# dc_dc.net
KiCad netlist of a schematic drawn in Altium Designer
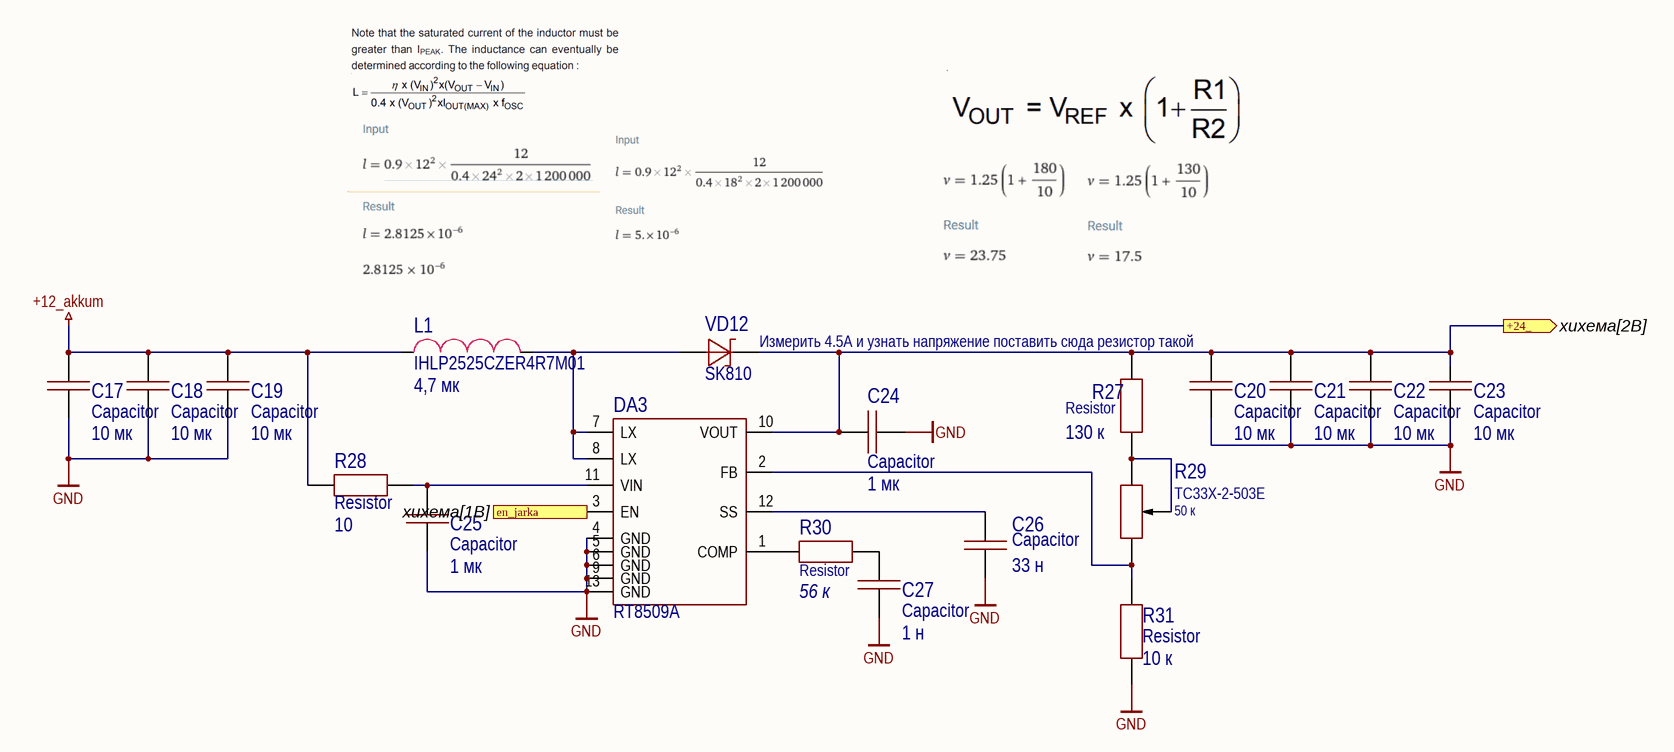
[diagram p0: dc dc жарить панели.SchDoc]

(export (version "E")
  (design (tool "Eeschema 10.0.6"))
  (components
    (comp (ref "C17")
      (value "Capacitor")
      (footprint "1210C")
      (description "Конденсатор")
      (fields
        (field (name "ALTIUM_VALUE") "10 мк")
        (field (name "PART NUMBER") "Capacitor_10u_10_35V_X7R_1210C")
        (field (name "TOLERANCE") "0,1")
      )
      (libsource (lib "Hydrolib") (part "Capacitor"))
    )
    (comp (ref "C18")
      (value "Capacitor")
      (footprint "1210C")
      (description "Конденсатор")
      (fields
        (field (name "ALTIUM_VALUE") "10 мк")
        (field (name "PART NUMBER") "Capacitor_10u_10_35V_X7R_1210C")
        (field (name "TOLERANCE") "0,1")
      )
      (libsource (lib "Hydrolib") (part "Capacitor"))
    )
    (comp (ref "C19")
      (value "Capacitor")
      (footprint "1210C")
      (description "Конденсатор")
      (fields
        (field (name "ALTIUM_VALUE") "10 мк")
        (field (name "PART NUMBER") "Capacitor_10u_10_35V_X7R_1210C")
        (field (name "TOLERANCE") "0,1")
      )
      (libsource (lib "Hydrolib") (part "Capacitor"))
    )
    (comp (ref "C20")
      (value "Capacitor")
      (footprint "1210C")
      (description "Конденсатор")
      (fields
        (field (name "ALTIUM_VALUE") "10 мк")
        (field (name "PART NUMBER") "Capacitor_10u_10_35V_X7R_1210C")
        (field (name "TOLERANCE") "0,1")
      )
      (libsource (lib "Hydrolib") (part "Capacitor"))
    )
    (comp (ref "C21")
      (value "Capacitor")
      (footprint "1210C")
      (description "Конденсатор")
      (fields
        (field (name "ALTIUM_VALUE") "10 мк")
        (field (name "PART NUMBER") "Capacitor_10u_10_35V_X7R_1210C")
        (field (name "TOLERANCE") "0,1")
      )
      (libsource (lib "Hydrolib") (part "Capacitor"))
    )
    (comp (ref "C22")
      (value "Capacitor")
      (footprint "1210C")
      (description "Конденсатор")
      (fields
        (field (name "ALTIUM_VALUE") "10 мк")
        (field (name "PART NUMBER") "Capacitor_10u_10_35V_X7R_1210C")
        (field (name "TOLERANCE") "0,1")
      )
      (libsource (lib "Hydrolib") (part "Capacitor"))
    )
    (comp (ref "C23")
      (value "Capacitor")
      (footprint "1210C")
      (description "Конденсатор")
      (fields
        (field (name "ALTIUM_VALUE") "10 мк")
        (field (name "PART NUMBER") "Capacitor_10u_10_35V_X7R_1210C")
        (field (name "TOLERANCE") "0,1")
      )
      (libsource (lib "Hydrolib") (part "Capacitor"))
    )
    (comp (ref "C24")
      (value "Capacitor")
      (footprint "0603C")
      (description "Конденсатор")
      (fields
        (field (name "ALTIUM_VALUE") "1 мк")
        (field (name "PART NUMBER") "Capacitor_1u_10_50V_X7R_0603C")
        (field (name "TOLERANCE") "0,1")
      )
      (libsource (lib "Hydrolib") (part "Capacitor"))
    )
    (comp (ref "C25")
      (value "Capacitor")
      (footprint "0603C")
      (description "Конденсатор")
      (fields
        (field (name "ALTIUM_VALUE") "1 мк")
        (field (name "PART NUMBER") "Capacitor_1u_10_50V_X7R_0603C")
        (field (name "TOLERANCE") "0,1")
      )
      (libsource (lib "Hydrolib") (part "Capacitor"))
    )
    (comp (ref "C26")
      (value "Capacitor")
      (footprint "0603C")
      (description "Конденсатор")
      (fields
        (field (name "ALTIUM_VALUE") "33 н")
        (field (name "PART NUMBER") "Capacitor_33n_10_50V_X7R_0603C")
        (field (name "TOLERANCE") "0,1")
      )
      (libsource (lib "Hydrolib") (part "Capacitor"))
    )
    (comp (ref "C27")
      (value "Capacitor")
      (footprint "0603C")
      (description "Конденсатор")
      (fields
        (field (name "ALTIUM_VALUE") "1 н")
        (field (name "PART NUMBER") "Capacitor_1n_10_50V_X7R_0603C")
        (field (name "TOLERANCE") "0,1")
      )
      (libsource (lib "Hydrolib") (part "Capacitor"))
    )
    (comp (ref "DA3")
      (value "RT8509A")
      (footprint "WDFN5x5-12")
      (description "Импульсный повышающий DC-DC стабилизатор, регулируемый, 2.8В-14В (Vin), 24В/4.5A, 1.5МГц, WDFN-12")
      (libsource (lib "Hydrolib") (part "RT8509A"))
    )
    (comp (ref "L1")
      (value "IHLP2525CZER4R7M01")
      (footprint "IHLP-2525")
      (description "ЧИП-индуктивность экранированная 4,7мкГн ±20% 5,5A 40мОм 2525")
      (fields (field (name "ALTIUM_VALUE") "4,7 мк"))
      (libsource (lib "Hydrolib") (part "Inductance"))
    )
    (comp (ref "R27")
      (value "Resistor")
      (footprint "0603R")
      (description "Резистор номиналом 130 кОм и точностью 1%")
      (fields
        (field (name "ALTIUM_VALUE") "130 к")
        (field (name "PART NUMBER") "Resistor_130k_1_0603")
        (field (name "TOLERANCE") "1%")
      )
      (libsource (lib "") (part "Resistor_2"))
    )
    (comp (ref "R28")
      (value "Resistor")
      (footprint "0603R")
      (description "Резистор номиналом 10 Ом и точностью 1%")
      (fields
        (field (name "ALTIUM_VALUE") "10")
        (field (name "PART NUMBER") "Resistor_10_1_0603")
        (field (name "TOLERANCE") "1%")
      )
      (libsource (lib "") (part "Resistor_3"))
    )
    (comp (ref "R29")
      (value "TC33X-2-503E")
      (footprint "3mm_trim")
      (description "Потенциометр однооборотный керметный 50кОм 0.1Вт ±25% SMD лента на катушке")
      (fields (field (name "ALTIUM_VALUE") "50 к") (field (name "TOLERANCE") "50%"))
      (libsource (lib "Hydrolib") (part "trim_res"))
    )
    (comp (ref "R30")
      (value "Resistor")
      (footprint "0603R")
      (description "Резистор номиналом 56 кОм и точностью 1%")
      (fields
        (field (name "ALTIUM_VALUE") "56 к")
        (field (name "PART NUMBER") "Resistor_56k_1_0603")
        (field (name "TOLERANCE") "1%")
      )
      (libsource (lib "Hydrolib") (part "Resistor"))
    )
    (comp (ref "R31")
      (value "Resistor")
      (footprint "0603R")
      (description "Резистор номиналом 10 кОм и точностью 1%")
      (fields
        (field (name "ALTIUM_VALUE") "10 к")
        (field (name "PART NUMBER") "Resistor_10k_1_0603")
        (field (name "TOLERANCE") "1%")
      )
      (libsource (lib "") (part "Resistor_1"))
    )
    (comp (ref "VD12")
      (value "SK810")
      (footprint "SMC")
      (description "Диод шоттки на 100 В, ном. ток 8 А")
      (libsource (lib "Hydrolib") (part "Schottky_diode"))
    )
  )
  (nets
    (net (code "1") (name "+12_akkum") (class "Default")
      (node (ref "C17") (pin "2") (pinfunction "2_2") (pintype "passive"))
      (node (ref "C18") (pin "2") (pinfunction "2_2") (pintype "passive"))
      (node (ref "C19") (pin "2") (pinfunction "2_2") (pintype "passive"))
      (node (ref "L1") (pin "1") (pinfunction "1_1") (pintype "passive"))
      (node (ref "R28") (pin "2") (pinfunction "2_2") (pintype "passive"))
    )
    (net (code "2") (name "/+24_") (class "Default")
      (node (ref "C20") (pin "2") (pinfunction "2_2") (pintype "passive"))
      (node (ref "C21") (pin "2") (pinfunction "2_2") (pintype "passive"))
      (node (ref "C22") (pin "2") (pinfunction "2_2") (pintype "passive"))
      (node (ref "C23") (pin "2") (pinfunction "2_2") (pintype "passive"))
      (node (ref "C24") (pin "1") (pinfunction "1_1") (pintype "passive"))
      (node (ref "DA3") (pin "10") (pinfunction "VOUT_10") (pintype "passive"))
      (node (ref "R27") (pin "2") (pinfunction "2_2") (pintype "passive"))
      (node (ref "VD12") (pin "2") (pinfunction "2_2") (pintype "passive"))
    )
    (net (code "3") (name "/en_jarka") (class "Default")
      (node (ref "DA3") (pin "3") (pinfunction "EN_3") (pintype "passive"))
    )
    (net (code "4") (name "GND") (class "Default")
      (node (ref "C17") (pin "1") (pinfunction "1_1") (pintype "passive"))
      (node (ref "C18") (pin "1") (pinfunction "1_1") (pintype "passive"))
      (node (ref "C19") (pin "1") (pinfunction "1_1") (pintype "passive"))
      (node (ref "C20") (pin "1") (pinfunction "1_1") (pintype "passive"))
      (node (ref "C21") (pin "1") (pinfunction "1_1") (pintype "passive"))
      (node (ref "C22") (pin "1") (pinfunction "1_1") (pintype "passive"))
      (node (ref "C23") (pin "1") (pinfunction "1_1") (pintype "passive"))
      (node (ref "C24") (pin "2") (pinfunction "2_2") (pintype "passive"))
      (node (ref "C25") (pin "1") (pinfunction "1_1") (pintype "passive"))
      (node (ref "C26") (pin "2") (pinfunction "2_2") (pintype "passive"))
      (node (ref "C27") (pin "1") (pinfunction "1_1") (pintype "passive"))
      (node (ref "DA3") (pin "13") (pinfunction "GND_13") (pintype "passive"))
      (node (ref "DA3") (pin "4") (pinfunction "GND_4") (pintype "passive"))
      (node (ref "DA3") (pin "5") (pinfunction "GND_5") (pintype "passive"))
      (node (ref "DA3") (pin "6") (pinfunction "GND_6") (pintype "passive"))
      (node (ref "DA3") (pin "9") (pinfunction "GND_9") (pintype "passive"))
      (node (ref "R31") (pin "2") (pinfunction "2_2") (pintype "passive"))
    )
    (net (code "5") (name "Net-(C27-Pad2)") (class "Default")
      (node (ref "C27") (pin "2") (pinfunction "2_2") (pintype "passive"))
      (node (ref "R30") (pin "2") (pinfunction "2_2") (pintype "passive"))
    )
    (net (code "6") (name "Net-(DA3-COMP)") (class "Default")
      (node (ref "DA3") (pin "1") (pinfunction "COMP_1") (pintype "passive"))
      (node (ref "R30") (pin "1") (pinfunction "1_1") (pintype "passive"))
    )
    (net (code "7") (name "Net-(DA3-FB)") (class "Default")
      (node (ref "DA3") (pin "2") (pinfunction "FB_2") (pintype "passive"))
      (node (ref "R29") (pin "3") (pinfunction "3_3") (pintype "passive"))
      (node (ref "R31") (pin "1") (pinfunction "1_1") (pintype "passive"))
    )
    (net (code "8") (name "Net-(DA3-LX-Pad7)") (class "Default")
      (node (ref "DA3") (pin "7") (pinfunction "LX_7") (pintype "passive"))
      (node (ref "DA3") (pin "8") (pinfunction "LX_8") (pintype "passive"))
      (node (ref "L1") (pin "2") (pinfunction "2_2") (pintype "passive"))
      (node (ref "VD12") (pin "1") (pinfunction "1_1") (pintype "passive"))
    )
    (net (code "9") (name "Net-(DA3-SS)") (class "Default")
      (node (ref "C26") (pin "1") (pinfunction "1_1") (pintype "passive"))
      (node (ref "DA3") (pin "12") (pinfunction "SS_12") (pintype "passive"))
    )
    (net (code "10") (name "Net-(DA3-VIN)") (class "Default")
      (node (ref "C25") (pin "2") (pinfunction "2_2") (pintype "passive"))
      (node (ref "DA3") (pin "11") (pinfunction "VIN_11") (pintype "passive"))
      (node (ref "R28") (pin "1") (pinfunction "1_1") (pintype "passive"))
    )
    (net (code "11") (name "Net-(R27-Pad1)") (class "Default")
      (node (ref "R27") (pin "1") (pinfunction "1_1") (pintype "passive"))
      (node (ref "R29") (pin "1") (pinfunction "1_1") (pintype "passive"))
      (node (ref "R29") (pin "2") (pinfunction "2_2") (pintype "passive"))
    )
  )
)
